# AD2_Breadboard_Breakout_v0_1.net
KiCad netlist of a schematic drawn in EAGLE
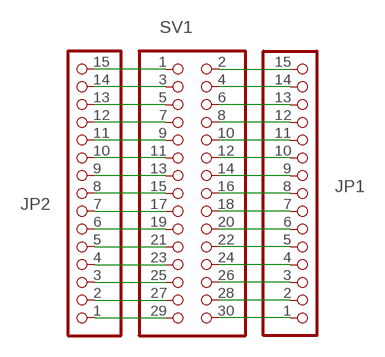
[diagram p0: schematic, sheet 1]

(export (version "E")
  (design (tool "Eeschema 10.0.6"))
  (components
    (comp (ref "JP1")
      (value "PINHD-1X15-CB")
      (footprint "eagle-import:1X15-CB")
      (libsource (lib "eagle-import") (part "PINHD-1X15-CB"))
    )
    (comp (ref "JP2")
      (value "PINHD-1X15-CB")
      (footprint "eagle-import:1X15-CB")
      (libsource (lib "eagle-import") (part "PINHD-1X15-CB"))
    )
    (comp (ref "SV1")
      (value "PINHD-2X15")
      (footprint "eagle-import:2X15")
      (libsource (lib "eagle-import") (part "PINHD-2X15"))
    )
  )
  (nets
    (net (code "1") (name "Net-(JP1-Pad1)") (class "Default")
      (node (ref "JP1") (pin "1") (pinfunction "1_1") (pintype "passive"))
      (node (ref "SV1") (pin "30") (pinfunction "30_30") (pintype "passive"))
    )
    (net (code "2") (name "Net-(JP1-Pad2)") (class "Default")
      (node (ref "JP1") (pin "2") (pinfunction "2_2") (pintype "passive"))
      (node (ref "SV1") (pin "28") (pinfunction "28_28") (pintype "passive"))
    )
    (net (code "3") (name "Net-(JP1-Pad3)") (class "Default")
      (node (ref "JP1") (pin "3") (pinfunction "3_3") (pintype "passive"))
      (node (ref "SV1") (pin "26") (pinfunction "26_26") (pintype "passive"))
    )
    (net (code "4") (name "Net-(JP1-Pad4)") (class "Default")
      (node (ref "JP1") (pin "4") (pinfunction "4_4") (pintype "passive"))
      (node (ref "SV1") (pin "24") (pinfunction "24_24") (pintype "passive"))
    )
    (net (code "5") (name "Net-(JP1-Pad5)") (class "Default")
      (node (ref "JP1") (pin "5") (pinfunction "5_5") (pintype "passive"))
      (node (ref "SV1") (pin "22") (pinfunction "22_22") (pintype "passive"))
    )
    (net (code "6") (name "Net-(JP1-Pad6)") (class "Default")
      (node (ref "JP1") (pin "6") (pinfunction "6_6") (pintype "passive"))
      (node (ref "SV1") (pin "20") (pinfunction "20_20") (pintype "passive"))
    )
    (net (code "7") (name "Net-(JP1-Pad7)") (class "Default")
      (node (ref "JP1") (pin "7") (pinfunction "7_7") (pintype "passive"))
      (node (ref "SV1") (pin "18") (pinfunction "18_18") (pintype "passive"))
    )
    (net (code "8") (name "Net-(JP1-Pad8)") (class "Default")
      (node (ref "JP1") (pin "8") (pinfunction "8_8") (pintype "passive"))
      (node (ref "SV1") (pin "16") (pinfunction "16_16") (pintype "passive"))
    )
    (net (code "9") (name "Net-(JP1-Pad9)") (class "Default")
      (node (ref "JP1") (pin "9") (pinfunction "9_9") (pintype "passive"))
      (node (ref "SV1") (pin "14") (pinfunction "14_14") (pintype "passive"))
    )
    (net (code "10") (name "Net-(JP1-Pad10)") (class "Default")
      (node (ref "JP1") (pin "10") (pinfunction "10_10") (pintype "passive"))
      (node (ref "SV1") (pin "12") (pinfunction "12_12") (pintype "passive"))
    )
    (net (code "11") (name "Net-(JP1-Pad11)") (class "Default")
      (node (ref "JP1") (pin "11") (pinfunction "11_11") (pintype "passive"))
      (node (ref "SV1") (pin "10") (pinfunction "10_10") (pintype "passive"))
    )
    (net (code "12") (name "Net-(JP1-Pad12)") (class "Default")
      (node (ref "JP1") (pin "12") (pinfunction "12_12") (pintype "passive"))
      (node (ref "SV1") (pin "8") (pinfunction "8_8") (pintype "passive"))
    )
    (net (code "13") (name "Net-(JP1-Pad13)") (class "Default")
      (node (ref "JP1") (pin "13") (pinfunction "13_13") (pintype "passive"))
      (node (ref "SV1") (pin "6") (pinfunction "6_6") (pintype "passive"))
    )
    (net (code "14") (name "Net-(JP1-Pad14)") (class "Default")
      (node (ref "JP1") (pin "14") (pinfunction "14_14") (pintype "passive"))
      (node (ref "SV1") (pin "4") (pinfunction "4_4") (pintype "passive"))
    )
    (net (code "15") (name "Net-(JP1-Pad15)") (class "Default")
      (node (ref "JP1") (pin "15") (pinfunction "15_15") (pintype "passive"))
      (node (ref "SV1") (pin "2") (pinfunction "2_2") (pintype "passive"))
    )
    (net (code "16") (name "Net-(JP2-Pad1)") (class "Default")
      (node (ref "JP2") (pin "1") (pinfunction "1_1") (pintype "passive"))
      (node (ref "SV1") (pin "29") (pinfunction "29_29") (pintype "passive"))
    )
    (net (code "17") (name "Net-(JP2-Pad2)") (class "Default")
      (node (ref "JP2") (pin "2") (pinfunction "2_2") (pintype "passive"))
      (node (ref "SV1") (pin "27") (pinfunction "27_27") (pintype "passive"))
    )
    (net (code "18") (name "Net-(JP2-Pad3)") (class "Default")
      (node (ref "JP2") (pin "3") (pinfunction "3_3") (pintype "passive"))
      (node (ref "SV1") (pin "25") (pinfunction "25_25") (pintype "passive"))
    )
    (net (code "19") (name "Net-(JP2-Pad4)") (class "Default")
      (node (ref "JP2") (pin "4") (pinfunction "4_4") (pintype "passive"))
      (node (ref "SV1") (pin "23") (pinfunction "23_23") (pintype "passive"))
    )
    (net (code "20") (name "Net-(JP2-Pad5)") (class "Default")
      (node (ref "JP2") (pin "5") (pinfunction "5_5") (pintype "passive"))
      (node (ref "SV1") (pin "21") (pinfunction "21_21") (pintype "passive"))
    )
    (net (code "21") (name "Net-(JP2-Pad6)") (class "Default")
      (node (ref "JP2") (pin "6") (pinfunction "6_6") (pintype "passive"))
      (node (ref "SV1") (pin "19") (pinfunction "19_19") (pintype "passive"))
    )
    (net (code "22") (name "Net-(JP2-Pad7)") (class "Default")
      (node (ref "JP2") (pin "7") (pinfunction "7_7") (pintype "passive"))
      (node (ref "SV1") (pin "17") (pinfunction "17_17") (pintype "passive"))
    )
    (net (code "23") (name "Net-(JP2-Pad8)") (class "Default")
      (node (ref "JP2") (pin "8") (pinfunction "8_8") (pintype "passive"))
      (node (ref "SV1") (pin "15") (pinfunction "15_15") (pintype "passive"))
    )
    (net (code "24") (name "Net-(JP2-Pad9)") (class "Default")
      (node (ref "JP2") (pin "9") (pinfunction "9_9") (pintype "passive"))
      (node (ref "SV1") (pin "13") (pinfunction "13_13") (pintype "passive"))
    )
    (net (code "25") (name "Net-(JP2-Pad10)") (class "Default")
      (node (ref "JP2") (pin "10") (pinfunction "10_10") (pintype "passive"))
      (node (ref "SV1") (pin "11") (pinfunction "11_11") (pintype "passive"))
    )
    (net (code "26") (name "Net-(JP2-Pad11)") (class "Default")
      (node (ref "JP2") (pin "11") (pinfunction "11_11") (pintype "passive"))
      (node (ref "SV1") (pin "9") (pinfunction "9_9") (pintype "passive"))
    )
    (net (code "27") (name "Net-(JP2-Pad12)") (class "Default")
      (node (ref "JP2") (pin "12") (pinfunction "12_12") (pintype "passive"))
      (node (ref "SV1") (pin "7") (pinfunction "7_7") (pintype "passive"))
    )
    (net (code "28") (name "Net-(JP2-Pad13)") (class "Default")
      (node (ref "JP2") (pin "13") (pinfunction "13_13") (pintype "passive"))
      (node (ref "SV1") (pin "5") (pinfunction "5_5") (pintype "passive"))
    )
    (net (code "29") (name "Net-(JP2-Pad14)") (class "Default")
      (node (ref "JP2") (pin "14") (pinfunction "14_14") (pintype "passive"))
      (node (ref "SV1") (pin "3") (pinfunction "3_3") (pintype "passive"))
    )
    (net (code "30") (name "Net-(JP2-Pad15)") (class "Default")
      (node (ref "JP2") (pin "15") (pinfunction "15_15") (pintype "passive"))
      (node (ref "SV1") (pin "1") (pinfunction "1_1") (pintype "passive"))
    )
  )
)
